# working.net
KiCad netlist of a schematic drawn in EAGLE
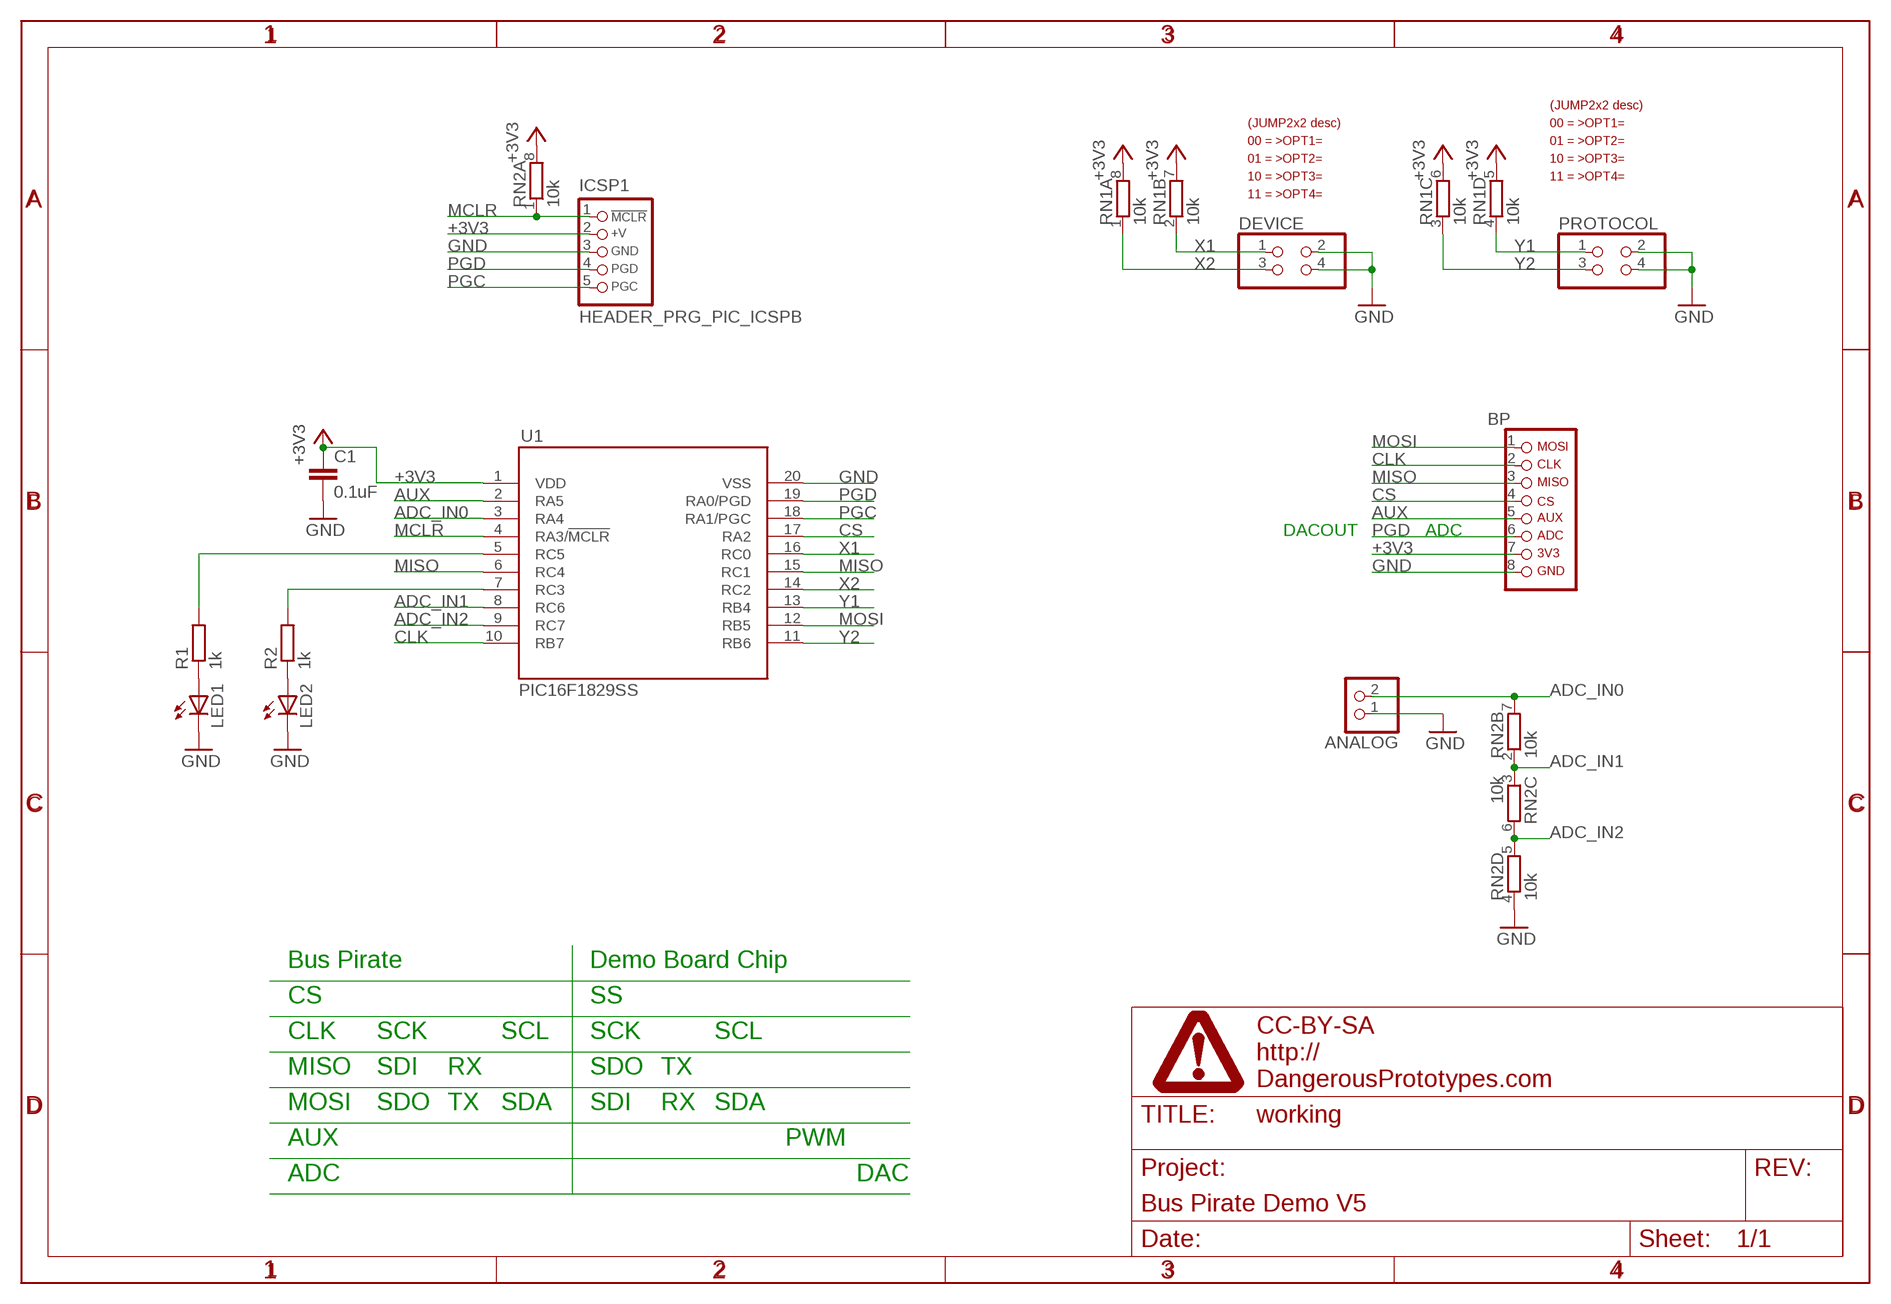
[diagram p0: schematic, sheet 1]

(export (version "E")
  (design (tool "Eeschema 10.0.6"))
  (components
    (comp (ref "ANALOG")
      (value "PINHD-1X2")
      (footprint "eagle-import:1X02")
      (libsource (lib "eagle-import") (part "PINHD-1X2"))
    )
    (comp (ref "BP")
      (value "HDR-BUSPIRATE")
      (footprint "eagle-import:HDR-BUSPIRATE")
      (libsource (lib "eagle-import") (part "HDR-BUSPIRATE"))
    )
    (comp (ref "C1")
      (value "0.1uF")
      (footprint "eagle-import:C603")
      (libsource (lib "eagle-import") (part "CAPC603"))
    )
    (comp (ref "DEVICE")
      (value "PINHD-2X2")
      (footprint "eagle-import:2X02")
      (libsource (lib "eagle-import") (part "PINHD-2X2"))
    )
    (comp (ref "ICSP1")
      (value "HEADER_PRG_PIC_ICSPB")
      (footprint "eagle-import:HEADER_PRG_1X05_ICSP_B")
      (libsource (lib "eagle-import") (part "HEADER_PRG_PIC_ICSPB"))
    )
    (comp (ref "LED1")
      (value "LED805")
      (footprint "eagle-import:LED-805")
      (libsource (lib "eagle-import") (part "LED805"))
    )
    (comp (ref "LED2")
      (value "LED805")
      (footprint "eagle-import:LED-805")
      (libsource (lib "eagle-import") (part "LED805"))
    )
    (comp (ref "PROTOCOL")
      (value "PINHD-2X2")
      (footprint "eagle-import:2X02")
      (libsource (lib "eagle-import") (part "PINHD-2X2"))
    )
    (comp (ref "R1")
      (value "1k")
      (footprint "eagle-import:R603")
      (libsource (lib "eagle-import") (part "RESISTORR603"))
    )
    (comp (ref "R2")
      (value "1k")
      (footprint "eagle-import:R603")
      (libsource (lib "eagle-import") (part "RESISTORR603"))
    )
    (comp (ref "RN1")
      (value "10k")
      (footprint "eagle-import:RN8P-4R-CRA06S")
      (libsource (lib "eagle-import") (part "RNETWORK"))
    )
    (comp (ref "RN2")
      (value "10k")
      (footprint "eagle-import:RN8P-4R-CRA06S")
      (libsource (lib "eagle-import") (part "RNETWORK"))
    )
    (comp (ref "U$1")
      (value "DINA4_L")
      (footprint "eagle-import:DP_LOGO")
      (fields
        (field (name "PROJECT") "Bus Pirate Demo V5")
        (field (name "LICENSE") "CC-BY-SA")
        (field (name "URL1") "http://")
        (field (name "URL2") "DangerousPrototypes.com")
        (field (name "PROJECT_1") "Bus Pirate Demo V5")
      )
      (libsource (lib "eagle-import") (part "DINA4_L"))
    )
    (comp (ref "U$9")
      (value "JUMP2X2_DESC")
      (footprint "eagle-import:JUMP2X2_DESC")
      (fields
        (field (name "OPT1") "SPI")
        (field (name "OPT2") "I2C")
        (field (name "OPT3") "UART")
        (field (name "OPT4") "____")
      )
      (libsource (lib "eagle-import") (part "JUMP2X2_DESC"))
    )
    (comp (ref "U$10")
      (value "JUMP2X2_DESC")
      (footprint "eagle-import:JUMP2X2_DESC")
      (fields
        (field (name "OPT1") "ADC")
        (field (name "OPT2") "DAC")
        (field (name "OPT3") "MEM")
        (field (name "OPT4") "PWM")
      )
      (libsource (lib "eagle-import") (part "JUMP2X2_DESC"))
    )
    (comp (ref "U1")
      (value "PIC16F1829SS")
      (footprint "eagle-import:SSOP20")
      (libsource (lib "eagle-import") (part "PIC16F1829SS"))
    )
  )
  (nets
    (net (code "1") (name "+3V3") (class "Default")
      (node (ref "BP") (pin "7") (pinfunction "7_7") (pintype "passive"))
      (node (ref "C1") (pin "1") (pinfunction "1_1") (pintype "passive"))
      (node (ref "ICSP1") (pin "2") (pinfunction "+V_2") (pintype "passive"))
      (node (ref "RN1") (pin "5") (pinfunction "2_5") (pintype "passive"))
      (node (ref "RN1") (pin "6") (pinfunction "2_6") (pintype "passive"))
      (node (ref "RN1") (pin "7") (pinfunction "2_7") (pintype "passive"))
      (node (ref "RN1") (pin "8") (pinfunction "2_8") (pintype "passive"))
      (node (ref "RN2") (pin "8") (pinfunction "2_8") (pintype "passive"))
      (node (ref "U1") (pin "1") (pinfunction "VDD_1") (pintype "power_in"))
    )
    (net (code "2") (name "/ADC_IN0") (class "Default")
      (node (ref "ANALOG") (pin "2") (pinfunction "2_2") (pintype "passive"))
      (node (ref "RN2") (pin "7") (pinfunction "2_7") (pintype "passive"))
      (node (ref "U1") (pin "3") (pinfunction "RA4_3") (pintype "bidirectional"))
    )
    (net (code "3") (name "/ADC_IN1") (class "Default")
      (node (ref "RN2") (pin "2") (pinfunction "1_2") (pintype "passive"))
      (node (ref "RN2") (pin "3") (pinfunction "1_3") (pintype "passive"))
      (node (ref "U1") (pin "8") (pinfunction "RC6_8") (pintype "bidirectional"))
    )
    (net (code "4") (name "/ADC_IN2") (class "Default")
      (node (ref "RN2") (pin "5") (pinfunction "2_5") (pintype "passive"))
      (node (ref "RN2") (pin "6") (pinfunction "2_6") (pintype "passive"))
      (node (ref "U1") (pin "9") (pinfunction "RC7_9") (pintype "bidirectional"))
    )
    (net (code "5") (name "/AUX") (class "Default")
      (node (ref "BP") (pin "5") (pinfunction "5_5") (pintype "passive"))
      (node (ref "U1") (pin "2") (pinfunction "RA5_2") (pintype "bidirectional"))
    )
    (net (code "6") (name "/CLK") (class "Default")
      (node (ref "BP") (pin "2") (pinfunction "2_2") (pintype "passive"))
      (node (ref "U1") (pin "10") (pinfunction "RB7_10") (pintype "bidirectional"))
    )
    (net (code "7") (name "/CS") (class "Default")
      (node (ref "BP") (pin "4") (pinfunction "4_4") (pintype "passive"))
      (node (ref "U1") (pin "17") (pinfunction "RA2_17") (pintype "bidirectional"))
    )
    (net (code "8") (name "/MCLR") (class "Default")
      (node (ref "ICSP1") (pin "1") (pinfunction "/MCLR_1") (pintype "passive"))
      (node (ref "RN2") (pin "1") (pinfunction "1_1") (pintype "passive"))
      (node (ref "U1") (pin "4") (pinfunction "RA3/~{MCLR}_4") (pintype "input"))
    )
    (net (code "9") (name "/MISO") (class "Default")
      (node (ref "BP") (pin "3") (pinfunction "3_3") (pintype "passive"))
      (node (ref "U1") (pin "15") (pinfunction "RC1_15") (pintype "bidirectional"))
      (node (ref "U1") (pin "6") (pinfunction "RC4_6") (pintype "bidirectional"))
    )
    (net (code "10") (name "/MOSI") (class "Default")
      (node (ref "BP") (pin "1") (pinfunction "1_1") (pintype "passive"))
      (node (ref "U1") (pin "12") (pinfunction "RB5_12") (pintype "bidirectional"))
    )
    (net (code "11") (name "/PGC") (class "Default")
      (node (ref "ICSP1") (pin "5") (pinfunction "PGC_5") (pintype "passive"))
      (node (ref "U1") (pin "18") (pinfunction "RA1/PGC_18") (pintype "bidirectional"))
    )
    (net (code "12") (name "/PGD") (class "Default")
      (node (ref "BP") (pin "6") (pinfunction "6_6") (pintype "passive"))
      (node (ref "ICSP1") (pin "4") (pinfunction "PGD_4") (pintype "passive"))
      (node (ref "U1") (pin "19") (pinfunction "RA0/PGD_19") (pintype "bidirectional"))
    )
    (net (code "13") (name "/X1") (class "Default")
      (node (ref "DEVICE") (pin "1") (pinfunction "1_1") (pintype "passive"))
      (node (ref "RN1") (pin "2") (pinfunction "1_2") (pintype "passive"))
      (node (ref "U1") (pin "16") (pinfunction "RC0_16") (pintype "bidirectional"))
    )
    (net (code "14") (name "/X2") (class "Default")
      (node (ref "DEVICE") (pin "3") (pinfunction "3_3") (pintype "passive"))
      (node (ref "RN1") (pin "1") (pinfunction "1_1") (pintype "passive"))
      (node (ref "U1") (pin "14") (pinfunction "RC2_14") (pintype "bidirectional"))
    )
    (net (code "15") (name "/Y1") (class "Default")
      (node (ref "PROTOCOL") (pin "1") (pinfunction "1_1") (pintype "passive"))
      (node (ref "RN1") (pin "4") (pinfunction "1_4") (pintype "passive"))
      (node (ref "U1") (pin "13") (pinfunction "RB4_13") (pintype "bidirectional"))
    )
    (net (code "16") (name "/Y2") (class "Default")
      (node (ref "PROTOCOL") (pin "3") (pinfunction "3_3") (pintype "passive"))
      (node (ref "RN1") (pin "3") (pinfunction "1_3") (pintype "passive"))
      (node (ref "U1") (pin "11") (pinfunction "RB6_11") (pintype "bidirectional"))
    )
    (net (code "17") (name "GND") (class "Default")
      (node (ref "ANALOG") (pin "1") (pinfunction "1_1") (pintype "passive"))
      (node (ref "BP") (pin "8") (pinfunction "8_8") (pintype "passive"))
      (node (ref "C1") (pin "2") (pinfunction "2_2") (pintype "passive"))
      (node (ref "DEVICE") (pin "2") (pinfunction "2_2") (pintype "passive"))
      (node (ref "DEVICE") (pin "4") (pinfunction "4_4") (pintype "passive"))
      (node (ref "ICSP1") (pin "3") (pinfunction "GND_3") (pintype "passive"))
      (node (ref "LED1") (pin "C") (pinfunction "C_C") (pintype "passive"))
      (node (ref "LED2") (pin "C") (pinfunction "C_C") (pintype "passive"))
      (node (ref "PROTOCOL") (pin "2") (pinfunction "2_2") (pintype "passive"))
      (node (ref "PROTOCOL") (pin "4") (pinfunction "4_4") (pintype "passive"))
      (node (ref "RN2") (pin "4") (pinfunction "1_4") (pintype "passive"))
      (node (ref "U1") (pin "20") (pinfunction "VSS_20") (pintype "power_in"))
    )
    (net (code "18") (name "Net-(LED1-PadA)") (class "Default")
      (node (ref "LED1") (pin "A") (pinfunction "A_A") (pintype "passive"))
      (node (ref "R1") (pin "1") (pinfunction "1_1") (pintype "passive"))
    )
    (net (code "19") (name "Net-(LED2-PadA)") (class "Default")
      (node (ref "LED2") (pin "A") (pinfunction "A_A") (pintype "passive"))
      (node (ref "R2") (pin "1") (pinfunction "1_1") (pintype "passive"))
    )
    (net (code "20") (name "Net-(U1-RC3)") (class "Default")
      (node (ref "R2") (pin "2") (pinfunction "2_2") (pintype "passive"))
      (node (ref "U1") (pin "7") (pinfunction "RC3_7") (pintype "bidirectional"))
    )
    (net (code "21") (name "Net-(U1-RC5)") (class "Default")
      (node (ref "R1") (pin "2") (pinfunction "2_2") (pintype "passive"))
      (node (ref "U1") (pin "5") (pinfunction "RC5_5") (pintype "bidirectional"))
    )
  )
)
